# SolBout.net
KiCad netlist of a schematic drawn in Altium Designer
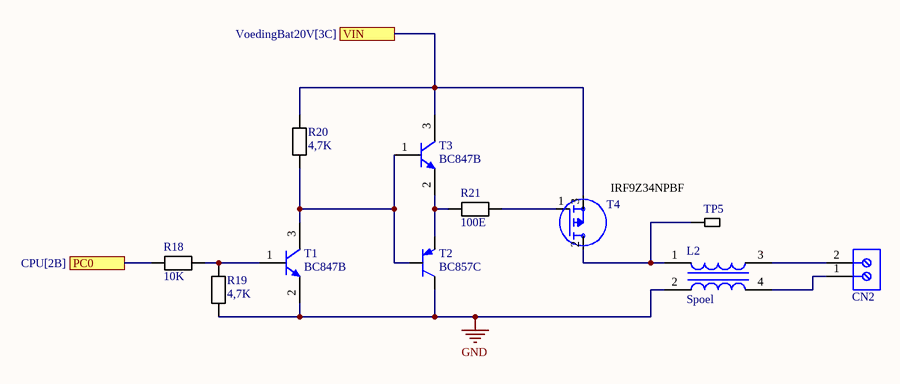
[diagram p0: SolBout.SchDoc]

(export (version "E")
  (design (tool "Eeschema 10.0.6"))
  (components
    (comp (ref "CN2")
      (value "1725656")
      (footprint "2 pinHeader")
      (fields (field (name "MANUFACTURER") "Phoenix Contact"))
      (libsource (lib "Schlib1") (part "2Pin-Header"))
    )
    (comp (ref "L2")
      (value "Spoel")
      (footprint "Spoel")
      (description "2 Line Common Mode Choke Through Hole 170 Ohms @ 100 MHz 10A DCR 10mOhm CM2545X171B-10")
      (fields (field (name "MF") "Laird") (field (name "MP") "CM2545X171B-10"))
      (libsource (lib "Schlib1") (part "Spoel"))
    )
    (comp (ref "R18")
      (value "10K")
      (footprint "REST")
      (fields (field (name "MANUFACTURER") "Vishay Dale") (field (name "PART NUMBER") "CRCW08050000Z0EA"))
      (libsource (lib "Schlib1") (part "resistor"))
    )
    (comp (ref "R19")
      (value "4,7K")
      (footprint "REST")
      (fields (field (name "MANUFACTURER") "Vishay Dale") (field (name "PART NUMBER") "CRCW08050000Z0EA"))
      (libsource (lib "Schlib1") (part "resistor"))
    )
    (comp (ref "R20")
      (value "4,7K")
      (footprint "REST")
      (fields (field (name "MANUFACTURER") "Vishay Dale") (field (name "PART NUMBER") "CRCW08050000Z0EA"))
      (libsource (lib "Schlib1") (part "resistor"))
    )
    (comp (ref "R21")
      (value "100E")
      (footprint "REST")
      (fields (field (name "MANUFACTURER") "Vishay Dale") (field (name "PART NUMBER") "CRCW08050000Z0EA"))
      (libsource (lib "Schlib1") (part "resistor"))
    )
    (comp (ref "T1")
      (value "BC847B")
      (footprint "TRANS")
      (fields (field (name "MANUFACTURER") "On Semiconductor") (field (name "PARTNUMBER") "BC547C"))
      (libsource (lib "Schlib1") (part "Transistor"))
    )
    (comp (ref "T2")
      (value "BC857C")
      (footprint "SOT95P240X120-3N")
      (description "BJT, SOT-23, 45V, 100mA, PNP, 0.25W, 150C")
      (fields (field (name "MF") "Diotec") (field (name "MP") "BC857B"))
      (libsource (lib "Schlib1") (part "BC857B"))
    )
    (comp (ref "T3")
      (value "BC847B")
      (footprint "TRANS")
      (fields (field (name "MANUFACTURER") "On Semiconductor") (field (name "PARTNUMBER") "BC547C"))
      (libsource (lib "Schlib1") (part "Transistor"))
    )
    (comp (ref "T4")
      (value "MOSFET")
      (footprint "TO254P1041X444X1930-3")
      (description "P-Channel 60V 18A _Tc_ 3.7W _Ta_, 88W _Tc_ Surface Mount D2PAK IRF9Z34SPBF")
      (fields (field (name "MF") "Vishay") (field (name "MP") "IRF9Z34SPBF"))
      (libsource (lib "Schlib1") (part "MOSFET"))
    )
    (comp (ref "TP5")
      (value "TP")
      (footprint "TP")
      (fields (field (name "PART NUMBER") "GRM1885C1H100JA01D") (field (name "MANUFACTURER") "Murata"))
      (libsource (lib "Schlib1") (part "TP"))
    )
  )
  (nets
    (net (code "1") (name "/PC0") (class "Default")
      (node (ref "R18") (pin "1") (pinfunction "1_1") (pintype "passive"))
    )
    (net (code "2") (name "/VIN") (class "Default")
      (node (ref "R20") (pin "2") (pinfunction "2_2") (pintype "passive"))
      (node (ref "T3") (pin "3") (pinfunction "C_3") (pintype "passive"))
      (node (ref "T4") (pin "3") (pinfunction "S_3") (pintype "passive"))
    )
    (net (code "3") (name "GND") (class "Default")
      (node (ref "L2") (pin "2") (pinfunction "2_2") (pintype "passive"))
      (node (ref "R19") (pin "1") (pinfunction "1_1") (pintype "passive"))
      (node (ref "T1") (pin "2") (pinfunction "E_2") (pintype "passive"))
      (node (ref "T2") (pin "3") (pinfunction "C_3") (pintype "passive"))
    )
    (net (code "4") (name "Net-(CN2-Pad1)") (class "Default")
      (node (ref "CN2") (pin "1") (pinfunction "1_1") (pintype "passive"))
      (node (ref "L2") (pin "4") (pinfunction "4_4") (pintype "passive"))
    )
    (net (code "5") (name "Net-(CN2-Pad2)") (class "Default")
      (node (ref "CN2") (pin "2") (pinfunction "2_2") (pintype "passive"))
      (node (ref "L2") (pin "3") (pinfunction "3_3") (pintype "passive"))
    )
    (net (code "6") (name "Net-(T1-B)") (class "Default")
      (node (ref "R18") (pin "2") (pinfunction "2_2") (pintype "passive"))
      (node (ref "R19") (pin "2") (pinfunction "2_2") (pintype "passive"))
      (node (ref "T1") (pin "1") (pinfunction "B_1") (pintype "passive"))
    )
    (net (code "7") (name "Net-(T1-C)") (class "Default")
      (node (ref "R20") (pin "1") (pinfunction "1_1") (pintype "passive"))
      (node (ref "T1") (pin "3") (pinfunction "C_3") (pintype "passive"))
      (node (ref "T2") (pin "1") (pinfunction "B_1") (pintype "passive"))
      (node (ref "T3") (pin "1") (pinfunction "B_1") (pintype "passive"))
    )
    (net (code "8") (name "Net-(T2-E)") (class "Default")
      (node (ref "R21") (pin "1") (pinfunction "1_1") (pintype "passive"))
      (node (ref "T2") (pin "2") (pinfunction "E_2") (pintype "passive"))
      (node (ref "T3") (pin "2") (pinfunction "E_2") (pintype "passive"))
    )
    (net (code "9") (name "Net-(T4-D)") (class "Default")
      (node (ref "L2") (pin "1") (pinfunction "1_1") (pintype "passive"))
      (node (ref "T4") (pin "2") (pinfunction "D_2") (pintype "passive"))
      (node (ref "TP5") (pin "1") (pinfunction "1_1") (pintype "passive"))
    )
    (net (code "10") (name "Net-(T4-G)") (class "Default")
      (node (ref "R21") (pin "2") (pinfunction "2_2") (pintype "passive"))
      (node (ref "T4") (pin "1") (pinfunction "G_1") (pintype "passive"))
    )
  )
)
